# timerinsol.net
KiCad netlist of a schematic drawn in EAGLE
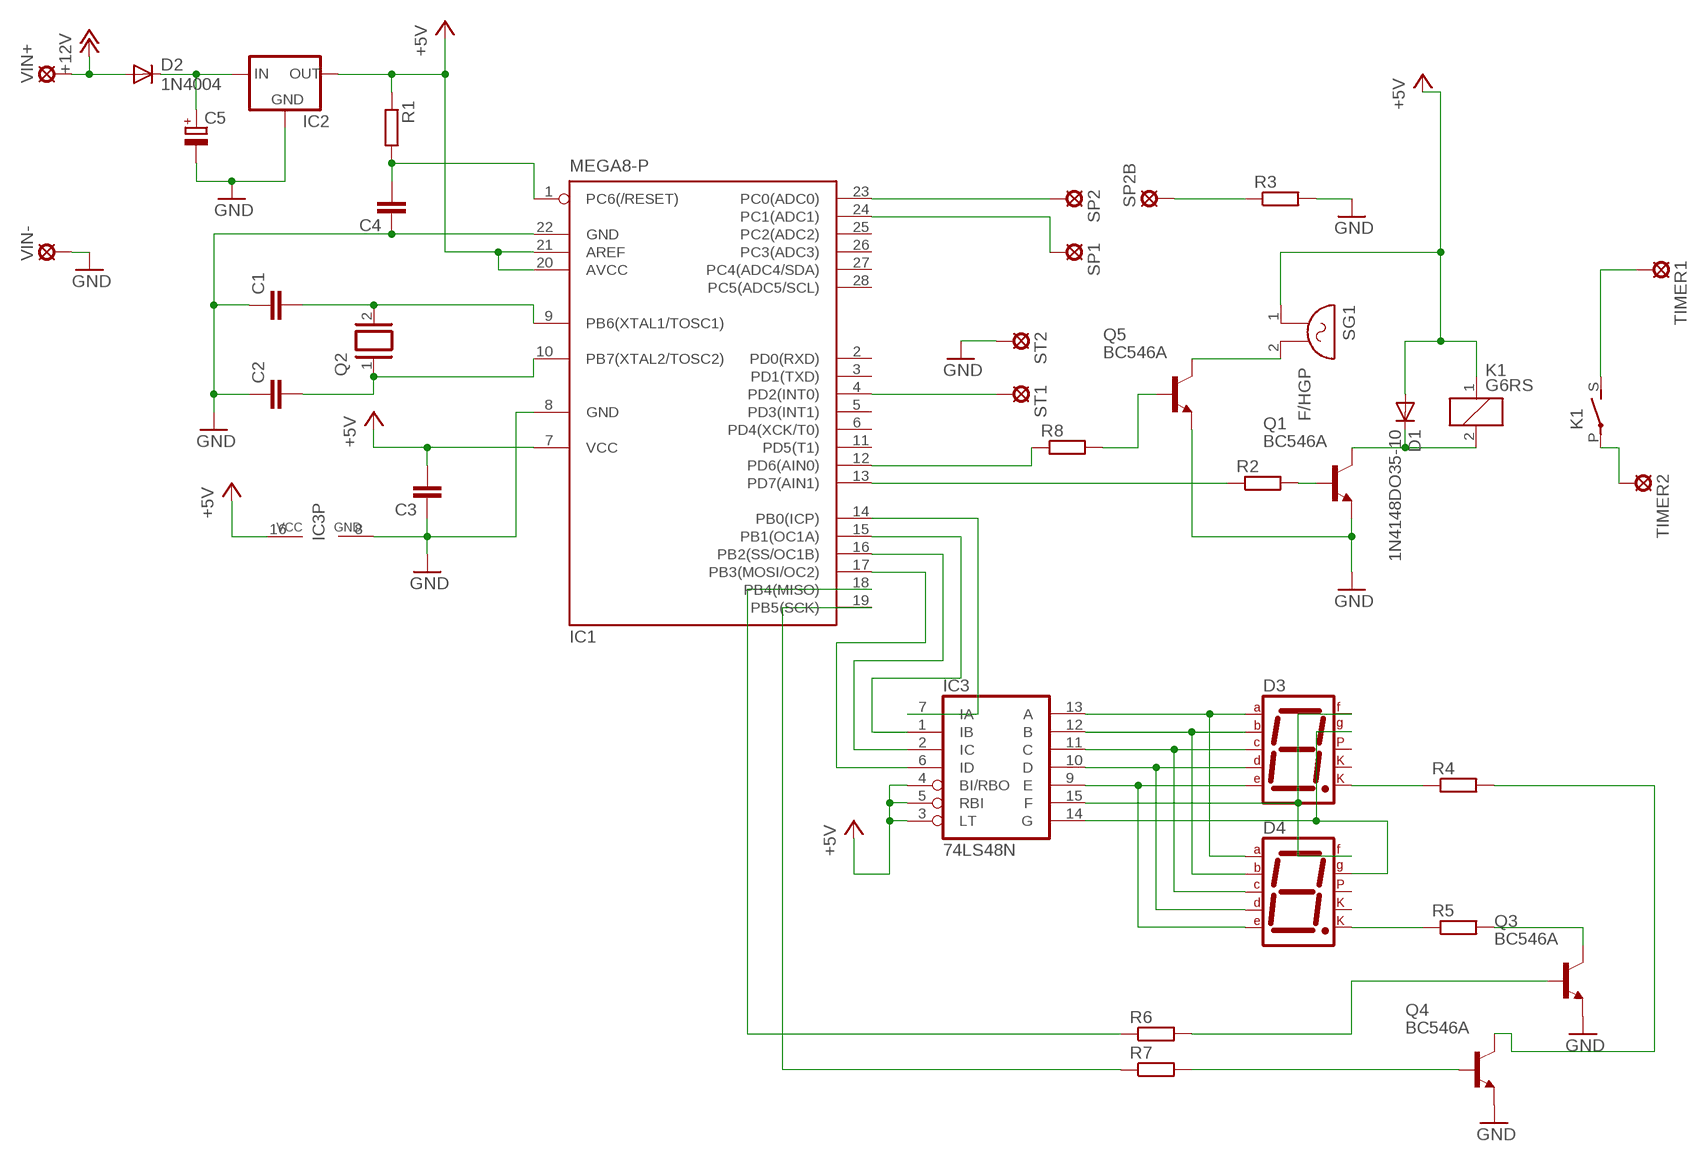
[diagram p0: schematic, sheet 1]

(export (version "E")
  (design (tool "Eeschema 10.0.6"))
  (components
    (comp (ref "C1")
      (value "C-EU025-025X050")
      (footprint "eagle-import:C025-025X050")
      (libsource (lib "eagle-import") (part "C-EU025-025X050"))
    )
    (comp (ref "C2")
      (value "C-EU025-025X050")
      (footprint "eagle-import:C025-025X050")
      (libsource (lib "eagle-import") (part "C-EU025-025X050"))
    )
    (comp (ref "C3")
      (value "C-EU025-025X050")
      (footprint "eagle-import:C025-025X050")
      (libsource (lib "eagle-import") (part "C-EU025-025X050"))
    )
    (comp (ref "C4")
      (value "C-EU025-025X050")
      (footprint "eagle-import:C025-025X050")
      (libsource (lib "eagle-import") (part "C-EU025-025X050"))
    )
    (comp (ref "C5")
      (value "CPOL-EUE2.5-6")
      (footprint "eagle-import:E2,5-6")
      (libsource (lib "eagle-import") (part "CPOL-EUE2.5-6"))
    )
    (comp (ref "D1")
      (value "1N4148DO35-10")
      (footprint "eagle-import:DO35-10")
      (libsource (lib "eagle-import") (part "1N4148DO35-10"))
    )
    (comp (ref "D2")
      (value "1N4004")
      (footprint "eagle-import:DO41-10")
      (libsource (lib "eagle-import") (part "1N4004"))
    )
    (comp (ref "D3")
      (value "7SEG-CK")
      (footprint "eagle-import:7SEG-13")
      (libsource (lib "eagle-import") (part "7SEG-CK"))
    )
    (comp (ref "D4")
      (value "7SEG-CK")
      (footprint "eagle-import:7SEG-13")
      (libsource (lib "eagle-import") (part "7SEG-CK"))
    )
    (comp (ref "IC1")
      (value "MEGA8-P")
      (footprint "eagle-import:DIL28-3")
      (libsource (lib "eagle-import") (part "MEGA8-P"))
    )
    (comp (ref "IC2")
      (value "78XXS")
      (footprint "eagle-import:78XXS")
      (libsource (lib "eagle-import") (part "78XXS"))
    )
    (comp (ref "IC3")
      (value "74LS48N")
      (footprint "eagle-import:DIL16")
      (libsource (lib "eagle-import") (part "7448NLS"))
    )
    (comp (ref "K1")
      (value "G6RS")
      (footprint "eagle-import:G6RS")
      (libsource (lib "eagle-import") (part "G6RS"))
    )
    (comp (ref "Q1")
      (value "BC546A")
      (footprint "eagle-import:TO92-EBC")
      (libsource (lib "eagle-import") (part "BC546A"))
    )
    (comp (ref "Q2")
      (value "XTAL/S")
      (footprint "eagle-import:QS")
      (libsource (lib "eagle-import") (part "XTAL/S"))
    )
    (comp (ref "Q3")
      (value "BC546A")
      (footprint "eagle-import:TO92-EBC")
      (libsource (lib "eagle-import") (part "BC546A"))
    )
    (comp (ref "Q4")
      (value "BC546A")
      (footprint "eagle-import:TO92-EBC")
      (libsource (lib "eagle-import") (part "BC546A"))
    )
    (comp (ref "Q5")
      (value "BC546A")
      (footprint "eagle-import:TO92-EBC")
      (libsource (lib "eagle-import") (part "BC546A"))
    )
    (comp (ref "R1")
      (value "R-EU_0204/7")
      (footprint "eagle-import:0204_7")
      (libsource (lib "eagle-import") (part "R-EU_0204/7"))
    )
    (comp (ref "R2")
      (value "R-EU_0207/5V")
      (footprint "eagle-import:0207_5V")
      (libsource (lib "eagle-import") (part "R-EU_0207/5V"))
    )
    (comp (ref "R3")
      (value "R-EU_0207/5V")
      (footprint "eagle-import:0207_5V")
      (libsource (lib "eagle-import") (part "R-EU_0207/5V"))
    )
    (comp (ref "R4")
      (value "R-EU_0207/5V")
      (footprint "eagle-import:0207_5V")
      (libsource (lib "eagle-import") (part "R-EU_0207/5V"))
    )
    (comp (ref "R5")
      (value "R-EU_0207/5V")
      (footprint "eagle-import:0207_5V")
      (libsource (lib "eagle-import") (part "R-EU_0207/5V"))
    )
    (comp (ref "R6")
      (value "R-EU_0207/5V")
      (footprint "eagle-import:0207_5V")
      (libsource (lib "eagle-import") (part "R-EU_0207/5V"))
    )
    (comp (ref "R7")
      (value "R-EU_0207/5V")
      (footprint "eagle-import:0207_5V")
      (libsource (lib "eagle-import") (part "R-EU_0207/5V"))
    )
    (comp (ref "R8")
      (value "R-EU_0207/5V")
      (footprint "eagle-import:0207_5V")
      (libsource (lib "eagle-import") (part "R-EU_0207/5V"))
    )
    (comp (ref "SG1")
      (value "F/HGP")
      (footprint "eagle-import:F_HGP")
      (libsource (lib "eagle-import") (part "F/HGP"))
    )
    (comp (ref "SP1")
      (value "LSP10")
      (footprint "eagle-import:LSP10")
      (libsource (lib "eagle-import") (part "LSP10"))
    )
    (comp (ref "SP2")
      (value "LSP10")
      (footprint "eagle-import:LSP10")
      (libsource (lib "eagle-import") (part "LSP10"))
    )
    (comp (ref "SP2B")
      (value "LSP10")
      (footprint "eagle-import:LSP10")
      (libsource (lib "eagle-import") (part "LSP10"))
    )
    (comp (ref "ST1")
      (value "LSP10")
      (footprint "eagle-import:LSP10")
      (libsource (lib "eagle-import") (part "LSP10"))
    )
    (comp (ref "ST2")
      (value "LSP10")
      (footprint "eagle-import:LSP10")
      (libsource (lib "eagle-import") (part "LSP10"))
    )
    (comp (ref "TIMER1")
      (value "LSP10")
      (footprint "eagle-import:LSP10")
      (libsource (lib "eagle-import") (part "LSP10"))
    )
    (comp (ref "TIMER2")
      (value "LSP10")
      (footprint "eagle-import:LSP10")
      (libsource (lib "eagle-import") (part "LSP10"))
    )
    (comp (ref "VIN+")
      (value "LSP10")
      (footprint "eagle-import:LSP10")
      (libsource (lib "eagle-import") (part "LSP10"))
    )
    (comp (ref "VIN-")
      (value "LSP10")
      (footprint "eagle-import:LSP10")
      (libsource (lib "eagle-import") (part "LSP10"))
    )
  )
  (nets
    (net (code "1") (name "+5V") (class "Default")
      (node (ref "C3") (pin "2") (pinfunction "2_2") (pintype "passive"))
      (node (ref "D1") (pin "A") (pinfunction "A_A") (pintype "passive"))
      (node (ref "IC1") (pin "20") (pinfunction "AVCC_20") (pintype "power_in"))
      (node (ref "IC1") (pin "21") (pinfunction "AREF_21") (pintype "passive"))
      (node (ref "IC1") (pin "7") (pinfunction "VCC_7") (pintype "power_in"))
      (node (ref "IC2") (pin "OUT") (pinfunction "OUT_OUT") (pintype "passive"))
      (node (ref "IC3") (pin "16") (pinfunction "VCC_16") (pintype "power_in"))
      (node (ref "IC3") (pin "3") (pinfunction "LT_3") (pintype "input"))
      (node (ref "IC3") (pin "4") (pinfunction "BI/RBO_4") (pintype "input"))
      (node (ref "IC3") (pin "5") (pinfunction "RBI_5") (pintype "input"))
      (node (ref "K1") (pin "1") (pinfunction "1_1") (pintype "passive"))
      (node (ref "R1") (pin "1") (pinfunction "1_1") (pintype "passive"))
      (node (ref "SG1") (pin "1") (pinfunction "1_1") (pintype "passive"))
    )
    (net (code "2") (name "+12V") (class "Default")
      (node (ref "D2") (pin "A") (pinfunction "A_A") (pintype "passive"))
      (node (ref "VIN+") (pin "MP") (pinfunction "MP_MP") (pintype "passive"))
    )
    (net (code "3") (name "GND") (class "Default")
      (node (ref "C1") (pin "1") (pinfunction "1_1") (pintype "passive"))
      (node (ref "C2") (pin "1") (pinfunction "1_1") (pintype "passive"))
      (node (ref "C3") (pin "1") (pinfunction "1_1") (pintype "passive"))
      (node (ref "C4") (pin "1") (pinfunction "1_1") (pintype "passive"))
      (node (ref "C5") (pin "-") (pinfunction "-_-") (pintype "passive"))
      (node (ref "IC1") (pin "22") (pinfunction "GND_22") (pintype "power_in"))
      (node (ref "IC1") (pin "8") (pinfunction "GND_8") (pintype "power_in"))
      (node (ref "IC2") (pin "GND") (pinfunction "GND_GND") (pintype "input"))
      (node (ref "IC3") (pin "8") (pinfunction "GND_8") (pintype "power_in"))
      (node (ref "Q1") (pin "E") (pinfunction "E_E") (pintype "passive"))
      (node (ref "Q3") (pin "E") (pinfunction "E_E") (pintype "passive"))
      (node (ref "Q4") (pin "E") (pinfunction "E_E") (pintype "passive"))
      (node (ref "Q5") (pin "E") (pinfunction "E_E") (pintype "passive"))
      (node (ref "R3") (pin "2") (pinfunction "2_2") (pintype "passive"))
      (node (ref "ST2") (pin "MP") (pinfunction "MP_MP") (pintype "passive"))
      (node (ref "VIN-") (pin "MP") (pinfunction "MP_MP") (pintype "passive"))
    )
    (net (code "4") (name "Net-(C5-Pad+)") (class "Default")
      (node (ref "C5") (pin "+") (pinfunction "+_+") (pintype "passive"))
      (node (ref "D2") (pin "C") (pinfunction "C_C") (pintype "passive"))
      (node (ref "IC2") (pin "IN") (pinfunction "IN_IN") (pintype "input"))
    )
    (net (code "5") (name "Net-(D1-PadC)") (class "Default")
      (node (ref "D1") (pin "C") (pinfunction "C_C") (pintype "passive"))
      (node (ref "K1") (pin "2") (pinfunction "2_2") (pintype "passive"))
      (node (ref "Q1") (pin "C") (pinfunction "C_C") (pintype "passive"))
    )
    (net (code "6") (name "Net-(D3-A)") (class "Default")
      (node (ref "D3") (pin "7") (pinfunction "A_7") (pintype "passive"))
      (node (ref "D4") (pin "7") (pinfunction "A_7") (pintype "passive"))
      (node (ref "IC3") (pin "13") (pinfunction "A_13") (pintype "output"))
    )
    (net (code "7") (name "Net-(D3-B)") (class "Default")
      (node (ref "D3") (pin "6") (pinfunction "B_6") (pintype "passive"))
      (node (ref "D4") (pin "6") (pinfunction "B_6") (pintype "passive"))
      (node (ref "IC3") (pin "12") (pinfunction "B_12") (pintype "output"))
    )
    (net (code "8") (name "Net-(D3-C)") (class "Default")
      (node (ref "D3") (pin "4") (pinfunction "C_4") (pintype "passive"))
      (node (ref "D4") (pin "4") (pinfunction "C_4") (pintype "passive"))
      (node (ref "IC3") (pin "11") (pinfunction "C_11") (pintype "output"))
    )
    (net (code "9") (name "Net-(D3-CK2)") (class "Default")
      (node (ref "D3") (pin "8") (pinfunction "CK2_8") (pintype "passive"))
      (node (ref "R4") (pin "1") (pinfunction "1_1") (pintype "passive"))
    )
    (net (code "10") (name "Net-(D3-D)") (class "Default")
      (node (ref "D3") (pin "2") (pinfunction "D_2") (pintype "passive"))
      (node (ref "D4") (pin "2") (pinfunction "D_2") (pintype "passive"))
      (node (ref "IC3") (pin "10") (pinfunction "D_10") (pintype "output"))
    )
    (net (code "11") (name "Net-(D3-E)") (class "Default")
      (node (ref "D3") (pin "1") (pinfunction "E_1") (pintype "passive"))
      (node (ref "D4") (pin "1") (pinfunction "E_1") (pintype "passive"))
      (node (ref "IC3") (pin "9") (pinfunction "E_9") (pintype "output"))
    )
    (net (code "12") (name "Net-(D3-F)") (class "Default")
      (node (ref "D3") (pin "9") (pinfunction "F_9") (pintype "passive"))
      (node (ref "D4") (pin "9") (pinfunction "F_9") (pintype "passive"))
      (node (ref "IC3") (pin "15") (pinfunction "F_15") (pintype "output"))
    )
    (net (code "13") (name "Net-(D3-G)") (class "Default")
      (node (ref "D3") (pin "10") (pinfunction "G_10") (pintype "passive"))
      (node (ref "D4") (pin "10") (pinfunction "G_10") (pintype "passive"))
      (node (ref "IC3") (pin "14") (pinfunction "G_14") (pintype "output"))
    )
    (net (code "14") (name "Net-(D4-CK2)") (class "Default")
      (node (ref "D4") (pin "8") (pinfunction "CK2_8") (pintype "passive"))
      (node (ref "R5") (pin "1") (pinfunction "1_1") (pintype "passive"))
    )
    (net (code "15") (name "Net-(IC1-PB0(ICP))") (class "Default")
      (node (ref "IC1") (pin "14") (pinfunction "PB0(ICP)_14") (pintype "bidirectional"))
      (node (ref "IC3") (pin "7") (pinfunction "IA_7") (pintype "input"))
    )
    (net (code "16") (name "Net-(IC1-PB1(OC1A))") (class "Default")
      (node (ref "IC1") (pin "15") (pinfunction "PB1(OC1A)_15") (pintype "bidirectional"))
      (node (ref "IC3") (pin "1") (pinfunction "IB_1") (pintype "input"))
    )
    (net (code "17") (name "Net-(IC1-PB2(SS{slash}OC1B))") (class "Default")
      (node (ref "IC1") (pin "16") (pinfunction "PB2(SS/OC1B)_16") (pintype "bidirectional"))
      (node (ref "IC3") (pin "2") (pinfunction "IC_2") (pintype "input"))
    )
    (net (code "18") (name "Net-(IC1-PB3(MOSI{slash}OC2))") (class "Default")
      (node (ref "IC1") (pin "17") (pinfunction "PB3(MOSI/OC2)_17") (pintype "bidirectional"))
      (node (ref "IC3") (pin "6") (pinfunction "ID_6") (pintype "input"))
    )
    (net (code "19") (name "Net-(IC1-PB4(MISO))") (class "Default")
      (node (ref "IC1") (pin "18") (pinfunction "PB4(MISO)_18") (pintype "bidirectional"))
      (node (ref "R6") (pin "1") (pinfunction "1_1") (pintype "passive"))
    )
    (net (code "20") (name "Net-(IC1-PB5(SCK))") (class "Default")
      (node (ref "IC1") (pin "19") (pinfunction "PB5(SCK)_19") (pintype "bidirectional"))
      (node (ref "R7") (pin "1") (pinfunction "1_1") (pintype "passive"))
    )
    (net (code "21") (name "Net-(IC1-PB6(XTAL1{slash}TOSC1))") (class "Default")
      (node (ref "C1") (pin "2") (pinfunction "2_2") (pintype "passive"))
      (node (ref "IC1") (pin "9") (pinfunction "PB6(XTAL1/TOSC1)_9") (pintype "bidirectional"))
      (node (ref "Q2") (pin "2") (pinfunction "2_2") (pintype "passive"))
    )
    (net (code "22") (name "Net-(IC1-PB7(XTAL2{slash}TOSC2))") (class "Default")
      (node (ref "C2") (pin "2") (pinfunction "2_2") (pintype "passive"))
      (node (ref "IC1") (pin "10") (pinfunction "PB7(XTAL2/TOSC2)_10") (pintype "bidirectional"))
      (node (ref "Q2") (pin "1") (pinfunction "1_1") (pintype "passive"))
    )
    (net (code "23") (name "Net-(IC1-PC0(ADC0))") (class "Default")
      (node (ref "IC1") (pin "23") (pinfunction "PC0(ADC0)_23") (pintype "bidirectional"))
      (node (ref "SP2") (pin "MP") (pinfunction "MP_MP") (pintype "passive"))
    )
    (net (code "24") (name "Net-(IC1-PC1(ADC1))") (class "Default")
      (node (ref "IC1") (pin "24") (pinfunction "PC1(ADC1)_24") (pintype "bidirectional"))
      (node (ref "SP1") (pin "MP") (pinfunction "MP_MP") (pintype "passive"))
    )
    (net (code "25") (name "Net-(IC1-PC6({slash}RESET))") (class "Default")
      (node (ref "C4") (pin "2") (pinfunction "2_2") (pintype "passive"))
      (node (ref "IC1") (pin "1") (pinfunction "PC6(/RESET)_1") (pintype "bidirectional"))
      (node (ref "R1") (pin "2") (pinfunction "2_2") (pintype "passive"))
    )
    (net (code "26") (name "Net-(IC1-PD2(INT0))") (class "Default")
      (node (ref "IC1") (pin "4") (pinfunction "PD2(INT0)_4") (pintype "bidirectional"))
      (node (ref "ST1") (pin "MP") (pinfunction "MP_MP") (pintype "passive"))
    )
    (net (code "27") (name "Net-(IC1-PD6(AIN0))") (class "Default")
      (node (ref "IC1") (pin "12") (pinfunction "PD6(AIN0)_12") (pintype "bidirectional"))
      (node (ref "R8") (pin "1") (pinfunction "1_1") (pintype "passive"))
    )
    (net (code "28") (name "Net-(IC1-PD7(AIN1))") (class "Default")
      (node (ref "IC1") (pin "13") (pinfunction "PD7(AIN1)_13") (pintype "bidirectional"))
      (node (ref "R2") (pin "1") (pinfunction "1_1") (pintype "passive"))
    )
    (net (code "29") (name "Net-(K1-PadP)") (class "Default")
      (node (ref "K1") (pin "P") (pinfunction "P_P") (pintype "passive"))
      (node (ref "TIMER2") (pin "MP") (pinfunction "MP_MP") (pintype "passive"))
    )
    (net (code "30") (name "Net-(K1-PadS)") (class "Default")
      (node (ref "K1") (pin "S") (pinfunction "S_S") (pintype "passive"))
      (node (ref "TIMER1") (pin "MP") (pinfunction "MP_MP") (pintype "passive"))
    )
    (net (code "31") (name "Net-(Q1-PadB)") (class "Default")
      (node (ref "Q1") (pin "B") (pinfunction "B_B") (pintype "passive"))
      (node (ref "R2") (pin "2") (pinfunction "2_2") (pintype "passive"))
    )
    (net (code "32") (name "Net-(Q3-PadB)") (class "Default")
      (node (ref "Q3") (pin "B") (pinfunction "B_B") (pintype "passive"))
      (node (ref "R6") (pin "2") (pinfunction "2_2") (pintype "passive"))
    )
    (net (code "33") (name "Net-(Q3-PadC)") (class "Default")
      (node (ref "Q3") (pin "C") (pinfunction "C_C") (pintype "passive"))
      (node (ref "R5") (pin "2") (pinfunction "2_2") (pintype "passive"))
    )
    (net (code "34") (name "Net-(Q4-PadB)") (class "Default")
      (node (ref "Q4") (pin "B") (pinfunction "B_B") (pintype "passive"))
      (node (ref "R7") (pin "2") (pinfunction "2_2") (pintype "passive"))
    )
    (net (code "35") (name "Net-(Q4-PadC)") (class "Default")
      (node (ref "Q4") (pin "C") (pinfunction "C_C") (pintype "passive"))
      (node (ref "R4") (pin "2") (pinfunction "2_2") (pintype "passive"))
    )
    (net (code "36") (name "Net-(Q5-PadB)") (class "Default")
      (node (ref "Q5") (pin "B") (pinfunction "B_B") (pintype "passive"))
      (node (ref "R8") (pin "2") (pinfunction "2_2") (pintype "passive"))
    )
    (net (code "37") (name "Net-(Q5-PadC)") (class "Default")
      (node (ref "Q5") (pin "C") (pinfunction "C_C") (pintype "passive"))
      (node (ref "SG1") (pin "2") (pinfunction "2_2") (pintype "passive"))
    )
    (net (code "38") (name "Net-(R3-Pad1)") (class "Default")
      (node (ref "R3") (pin "1") (pinfunction "1_1") (pintype "passive"))
      (node (ref "SP2B") (pin "MP") (pinfunction "MP_MP") (pintype "passive"))
    )
    (net (code "39") (name "unconnected-(D3-CK1-Pad3)") (class "Default")
      (node (ref "D3") (pin "3") (pinfunction "CK1_3") (pintype "passive"))
    )
    (net (code "40") (name "unconnected-(D3-DP-Pad5)") (class "Default")
      (node (ref "D3") (pin "5") (pinfunction "DP_5") (pintype "passive"))
    )
    (net (code "41") (name "unconnected-(D4-CK1-Pad3)") (class "Default")
      (node (ref "D4") (pin "3") (pinfunction "CK1_3") (pintype "passive"))
    )
    (net (code "42") (name "unconnected-(D4-DP-Pad5)") (class "Default")
      (node (ref "D4") (pin "5") (pinfunction "DP_5") (pintype "passive"))
    )
    (net (code "43") (name "unconnected-(IC1-PC2(ADC2)-Pad25)") (class "Default")
      (node (ref "IC1") (pin "25") (pinfunction "PC2(ADC2)_25") (pintype "bidirectional"))
    )
    (net (code "44") (name "unconnected-(IC1-PC3(ADC3)-Pad26)") (class "Default")
      (node (ref "IC1") (pin "26") (pinfunction "PC3(ADC3)_26") (pintype "bidirectional"))
    )
    (net (code "45") (name "unconnected-(IC1-PC4(ADC4{slash}SDA)-Pad27)") (class "Default")
      (node (ref "IC1") (pin "27") (pinfunction "PC4(ADC4/SDA)_27") (pintype "bidirectional"))
    )
    (net (code "46") (name "unconnected-(IC1-PC5(ADC5{slash}SCL)-Pad28)") (class "Default")
      (node (ref "IC1") (pin "28") (pinfunction "PC5(ADC5/SCL)_28") (pintype "bidirectional"))
    )
    (net (code "47") (name "unconnected-(IC1-PD0(RXD)-Pad2)") (class "Default")
      (node (ref "IC1") (pin "2") (pinfunction "PD0(RXD)_2") (pintype "bidirectional"))
    )
    (net (code "48") (name "unconnected-(IC1-PD1(TXD)-Pad3)") (class "Default")
      (node (ref "IC1") (pin "3") (pinfunction "PD1(TXD)_3") (pintype "bidirectional"))
    )
    (net (code "49") (name "unconnected-(IC1-PD3(INT1)-Pad5)") (class "Default")
      (node (ref "IC1") (pin "5") (pinfunction "PD3(INT1)_5") (pintype "bidirectional"))
    )
    (net (code "50") (name "unconnected-(IC1-PD4(XCK{slash}T0)-Pad6)") (class "Default")
      (node (ref "IC1") (pin "6") (pinfunction "PD4(XCK/T0)_6") (pintype "bidirectional"))
    )
    (net (code "51") (name "unconnected-(IC1-PD5(T1)-Pad11)") (class "Default")
      (node (ref "IC1") (pin "11") (pinfunction "PD5(T1)_11") (pintype "bidirectional"))
    )
  )
)
